# transmitter_receiver.net
KiCad netlist of a schematic drawn in EAGLE
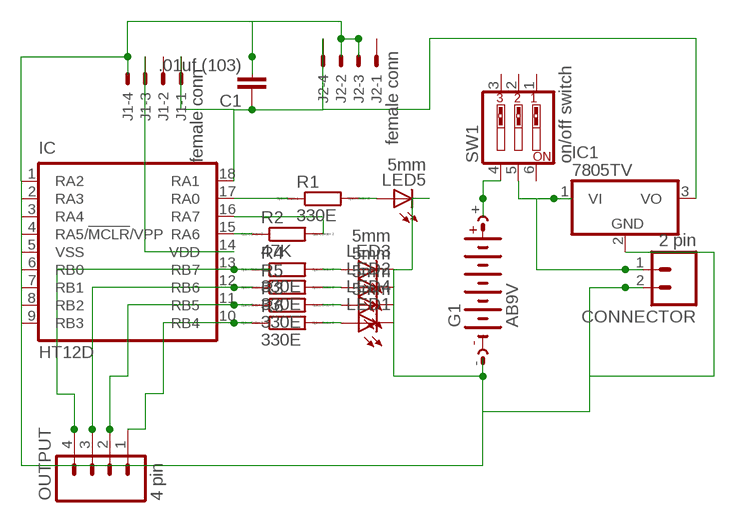
[diagram p0: schematic, sheet 1]

(export (version "E")
  (design (tool "Eeschema 10.0.6"))
  (components
    (comp (ref "C1")
      (value ".01uf (103)")
      (footprint "eagle-import:C2.5-2")
      (libsource (lib "eagle-import") (part "C2.5/2"))
    )
    (comp (ref "CONNECTOR")
      (value "2 pin")
      (footprint "eagle-import:02P")
      (libsource (lib "eagle-import") (part "M02"))
    )
    (comp (ref "G1")
      (value "AB9V")
      (footprint "eagle-import:AB9V")
      (libsource (lib "eagle-import") (part "AB9V"))
    )
    (comp (ref "IC")
      (value "HT12D")
      (footprint "eagle-import:DIL18")
      (libsource (lib "eagle-import") (part "PIC16F1826/27P"))
    )
    (comp (ref "IC1")
      (value "7805TV")
      (footprint "eagle-import:TO220V")
      (libsource (lib "eagle-import") (part "78TV05"))
    )
    (comp (ref "J1")
      (value "female conn")
      (footprint "eagle-import:7395-04")
      (libsource (lib "eagle-import") (part "22-?-0405-7048"))
    )
    (comp (ref "J2")
      (value "female conn")
      (footprint "eagle-import:7395-04")
      (libsource (lib "eagle-import") (part "22-?-0405-7048"))
    )
    (comp (ref "LED1")
      (value "5mm")
      (footprint "eagle-import:LED5MM")
      (libsource (lib "eagle-import") (part "LED5MM"))
    )
    (comp (ref "LED2")
      (value "5mm")
      (footprint "eagle-import:LED5MM")
      (libsource (lib "eagle-import") (part "LED5MM"))
    )
    (comp (ref "LED3")
      (value "5mm")
      (footprint "eagle-import:LED5MM")
      (libsource (lib "eagle-import") (part "LED5MM"))
    )
    (comp (ref "LED4")
      (value "5mm")
      (footprint "eagle-import:LED5MM")
      (libsource (lib "eagle-import") (part "LED5MM"))
    )
    (comp (ref "LED5")
      (value "5mm")
      (footprint "eagle-import:LED5MM")
      (libsource (lib "eagle-import") (part "LED5MM"))
    )
    (comp (ref "OUTPUT")
      (value "4 pin")
      (footprint "eagle-import:04P")
      (libsource (lib "eagle-import") (part "M04"))
    )
    (comp (ref "R1")
      (value "330E")
      (footprint "eagle-import:0207_10")
      (libsource (lib "eagle-import") (part "R0207/10"))
    )
    (comp (ref "R2")
      (value "47K")
      (footprint "eagle-import:0207_10")
      (libsource (lib "eagle-import") (part "R0207/10"))
    )
    (comp (ref "R3")
      (value "330E")
      (footprint "eagle-import:0207_10")
      (libsource (lib "eagle-import") (part "R0207/10"))
    )
    (comp (ref "R4")
      (value "330E")
      (footprint "eagle-import:0207_10")
      (libsource (lib "eagle-import") (part "R0207/10"))
    )
    (comp (ref "R5")
      (value "330E")
      (footprint "eagle-import:0207_10")
      (libsource (lib "eagle-import") (part "R0207/10"))
    )
    (comp (ref "R6")
      (value "330E")
      (footprint "eagle-import:0207_10")
      (libsource (lib "eagle-import") (part "R0207/10"))
    )
    (comp (ref "SW1")
      (value "on/off switch")
      (footprint "eagle-import:EDG-03")
      (libsource (lib "eagle-import") (part "SW_DIP-3"))
    )
  )
  (nets
    (net (code "1") (name "Net-(G1-Pad+)") (class "Default")
      (node (ref "G1") (pin "+") (pinfunction "+_+") (pintype "passive"))
      (node (ref "SW1") (pin "4") (pinfunction "4_4") (pintype "passive"))
    )
    (net (code "2") (name "Net-(IC-RA0)") (class "Default")
      (node (ref "IC") (pin "17") (pinfunction "RA0_17") (pintype "bidirectional"))
      (node (ref "R1") (pin "1") (pinfunction "1_1") (pintype "passive"))
    )
    (net (code "3") (name "Net-(IC-RA1)") (class "Default")
      (node (ref "C1") (pin "1") (pinfunction "1_1") (pintype "passive"))
      (node (ref "IC") (pin "18") (pinfunction "RA1_18") (pintype "bidirectional"))
      (node (ref "IC1") (pin "3") (pinfunction "VO_3") (pintype "passive"))
      (node (ref "J1") (pin "1") (pinfunction "S_1") (pintype "passive"))
      (node (ref "J2") (pin "4") (pinfunction "S_4") (pintype "passive"))
    )
    (net (code "4") (name "Net-(IC-RA2)") (class "Default")
      (node (ref "C1") (pin "2") (pinfunction "2_2") (pintype "passive"))
      (node (ref "CONNECTOR") (pin "2") (pinfunction "2_2") (pintype "passive"))
      (node (ref "G1") (pin "-") (pinfunction "-_-") (pintype "passive"))
      (node (ref "IC") (pin "1") (pinfunction "RA2_1") (pintype "bidirectional"))
      (node (ref "IC") (pin "2") (pinfunction "RA3_2") (pintype "bidirectional"))
      (node (ref "IC") (pin "3") (pinfunction "RA4_3") (pintype "bidirectional"))
      (node (ref "IC") (pin "4") (pinfunction "RA5/~{MCLR}/VPP_4") (pintype "bidirectional"))
      (node (ref "IC") (pin "5") (pinfunction "VSS_5") (pintype "power_in"))
      (node (ref "IC") (pin "6") (pinfunction "RB0_6") (pintype "bidirectional"))
      (node (ref "IC") (pin "7") (pinfunction "RB1_7") (pintype "bidirectional"))
      (node (ref "IC") (pin "8") (pinfunction "RB2_8") (pintype "bidirectional"))
      (node (ref "IC") (pin "9") (pinfunction "RB3_9") (pintype "bidirectional"))
      (node (ref "IC1") (pin "2") (pinfunction "GND_2") (pintype "passive"))
      (node (ref "J1") (pin "4") (pinfunction "S_4") (pintype "passive"))
      (node (ref "J2") (pin "2") (pinfunction "S_2") (pintype "passive"))
      (node (ref "J2") (pin "3") (pinfunction "S_3") (pintype "passive"))
      (node (ref "LED1") (pin "K") (pinfunction "C_K") (pintype "passive"))
      (node (ref "LED2") (pin "K") (pinfunction "C_K") (pintype "passive"))
      (node (ref "LED3") (pin "K") (pinfunction "C_K") (pintype "passive"))
      (node (ref "LED4") (pin "K") (pinfunction "C_K") (pintype "passive"))
      (node (ref "LED5") (pin "K") (pinfunction "C_K") (pintype "passive"))
    )
    (net (code "5") (name "Net-(IC-RA6)") (class "Default")
      (node (ref "IC") (pin "15") (pinfunction "RA6_15") (pintype "bidirectional"))
      (node (ref "R2") (pin "1") (pinfunction "1_1") (pintype "passive"))
    )
    (net (code "6") (name "Net-(IC-RA7)") (class "Default")
      (node (ref "IC") (pin "16") (pinfunction "RA7_16") (pintype "bidirectional"))
      (node (ref "R2") (pin "2") (pinfunction "2_2") (pintype "passive"))
    )
    (net (code "7") (name "Net-(IC-RB4)") (class "Default")
      (node (ref "IC") (pin "10") (pinfunction "RB4_10") (pintype "bidirectional"))
      (node (ref "OUTPUT") (pin "1") (pinfunction "1_1") (pintype "passive"))
      (node (ref "R6") (pin "1") (pinfunction "1_1") (pintype "passive"))
    )
    (net (code "8") (name "Net-(IC-RB5)") (class "Default")
      (node (ref "IC") (pin "11") (pinfunction "RB5_11") (pintype "bidirectional"))
      (node (ref "OUTPUT") (pin "2") (pinfunction "2_2") (pintype "passive"))
      (node (ref "R3") (pin "1") (pinfunction "1_1") (pintype "passive"))
    )
    (net (code "9") (name "Net-(IC-RB6)") (class "Default")
      (node (ref "IC") (pin "12") (pinfunction "RB6_12") (pintype "bidirectional"))
      (node (ref "OUTPUT") (pin "3") (pinfunction "3_3") (pintype "passive"))
      (node (ref "R5") (pin "1") (pinfunction "1_1") (pintype "passive"))
    )
    (net (code "10") (name "Net-(IC-RB7)") (class "Default")
      (node (ref "IC") (pin "13") (pinfunction "RB7_13") (pintype "bidirectional"))
      (node (ref "OUTPUT") (pin "4") (pinfunction "4_4") (pintype "passive"))
      (node (ref "R4") (pin "1") (pinfunction "1_1") (pintype "passive"))
    )
    (net (code "11") (name "Net-(IC-VDD)") (class "Default")
      (node (ref "IC") (pin "14") (pinfunction "VDD_14") (pintype "power_in"))
      (node (ref "J1") (pin "3") (pinfunction "S_3") (pintype "passive"))
    )
    (net (code "12") (name "Net-(IC1-VI)") (class "Default")
      (node (ref "CONNECTOR") (pin "1") (pinfunction "1_1") (pintype "passive"))
      (node (ref "IC1") (pin "1") (pinfunction "VI_1") (pintype "input"))
      (node (ref "SW1") (pin "5") (pinfunction "5_5") (pintype "passive"))
    )
    (net (code "13") (name "Net-(LED1-PadA)") (class "Default")
      (node (ref "LED1") (pin "A") (pinfunction "A_A") (pintype "passive"))
      (node (ref "R6") (pin "2") (pinfunction "2_2") (pintype "passive"))
    )
    (net (code "14") (name "Net-(LED2-PadA)") (class "Default")
      (node (ref "LED2") (pin "A") (pinfunction "A_A") (pintype "passive"))
      (node (ref "R5") (pin "2") (pinfunction "2_2") (pintype "passive"))
    )
    (net (code "15") (name "Net-(LED3-PadA)") (class "Default")
      (node (ref "LED3") (pin "A") (pinfunction "A_A") (pintype "passive"))
      (node (ref "R4") (pin "2") (pinfunction "2_2") (pintype "passive"))
    )
    (net (code "16") (name "Net-(LED4-PadA)") (class "Default")
      (node (ref "LED4") (pin "A") (pinfunction "A_A") (pintype "passive"))
      (node (ref "R3") (pin "2") (pinfunction "2_2") (pintype "passive"))
    )
    (net (code "17") (name "Net-(LED5-PadA)") (class "Default")
      (node (ref "LED5") (pin "A") (pinfunction "A_A") (pintype "passive"))
      (node (ref "R1") (pin "2") (pinfunction "2_2") (pintype "passive"))
    )
    (net (code "18") (name "unconnected-(J1B-S-Pad2)") (class "Default")
      (node (ref "J1") (pin "2") (pinfunction "S_2") (pintype "passive"))
    )
    (net (code "19") (name "unconnected-(J2A-S-Pad1)") (class "Default")
      (node (ref "J2") (pin "1") (pinfunction "S_1") (pintype "passive"))
    )
    (net (code "20") (name "unconnected-(SW1-Pad1)") (class "Default")
      (node (ref "SW1") (pin "1") (pinfunction "1_1") (pintype "passive"))
    )
    (net (code "21") (name "unconnected-(SW1-Pad2)") (class "Default")
      (node (ref "SW1") (pin "2") (pinfunction "2_2") (pintype "passive"))
    )
    (net (code "22") (name "unconnected-(SW1-Pad3)") (class "Default")
      (node (ref "SW1") (pin "3") (pinfunction "3_3") (pintype "passive"))
    )
    (net (code "23") (name "unconnected-(SW1-Pad6)") (class "Default")
      (node (ref "SW1") (pin "6") (pinfunction "6_6") (pintype "passive"))
    )
  )
)
